# atxmega128a1.net
KiCad netlist of a schematic drawn in Altium Designer
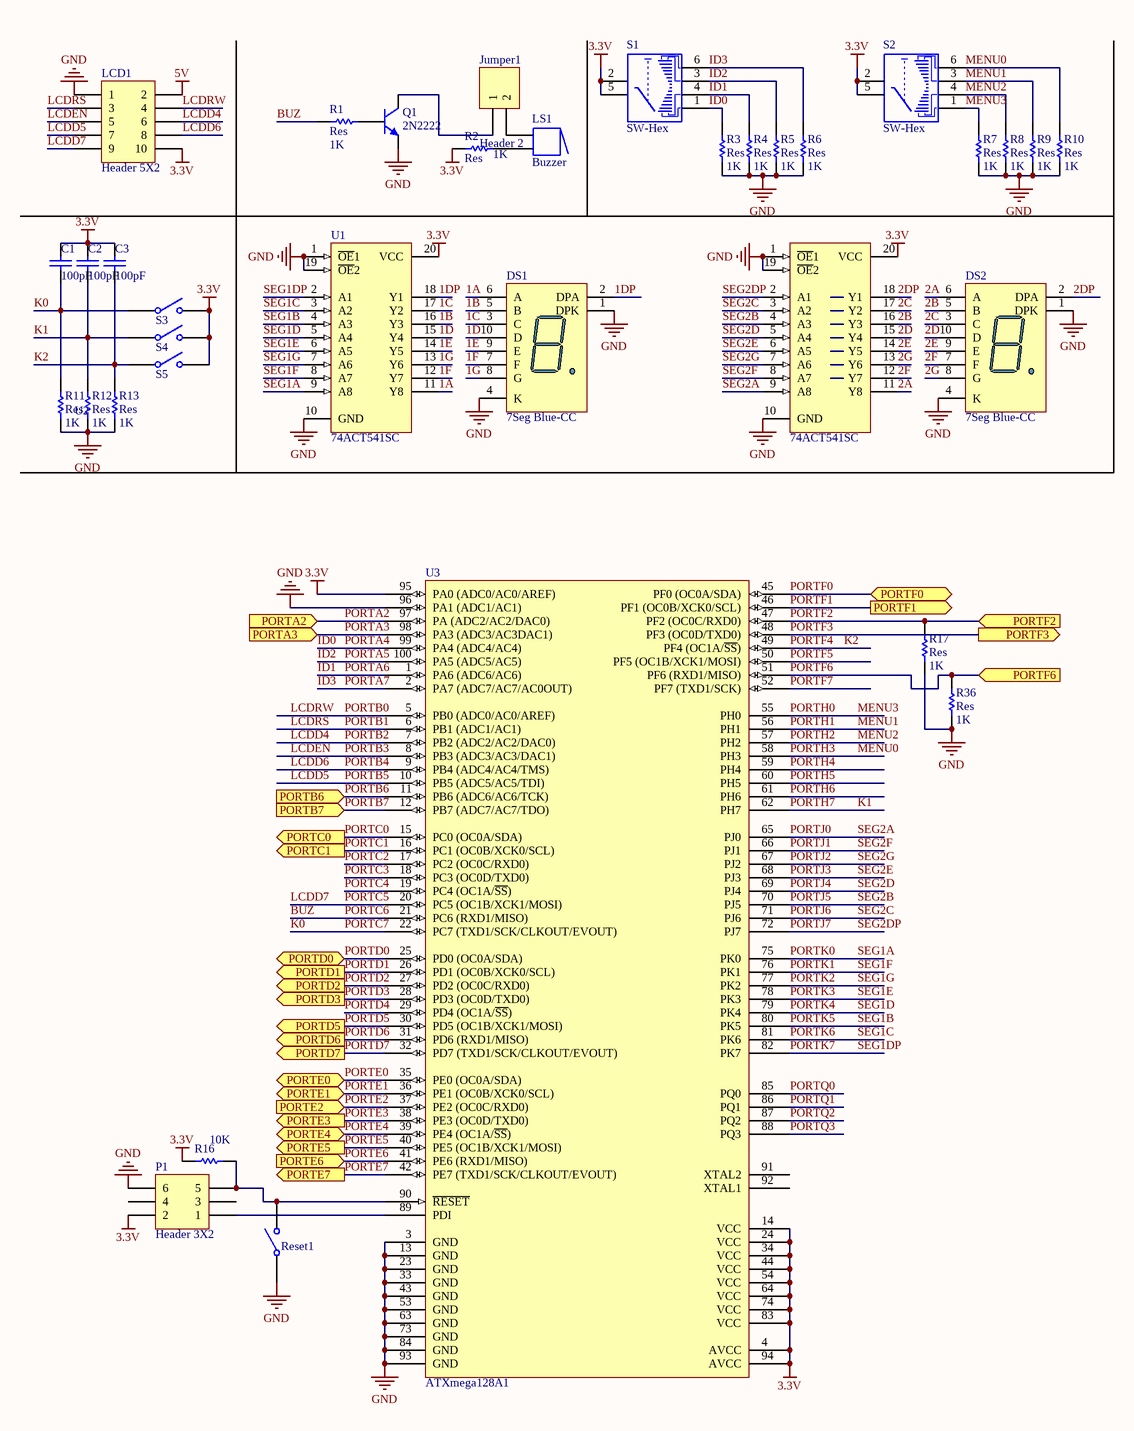
[diagram p0: atxmega128a1.SchDoc]

(export (version "E")
  (design (tool "Eeschema 10.0.6"))
  (components
    (comp (ref "C1")
      (value "100pF")
      (footprint "2012[0805]")
      (description "Capacitor")
      (fields (field (name "Comment") "Cap_UP") (field (name "PUBLISHER") "Altium Limited"))
      (libsource (lib "KN2CLib") (part "Cap_UP"))
    )
    (comp (ref "C2")
      (value "100pF")
      (footprint "2012[0805]")
      (description "Capacitor")
      (fields (field (name "Comment") "Cap_UP") (field (name "PUBLISHER") "Altium Limited"))
      (libsource (lib "KN2CLib") (part "Cap_UP"))
    )
    (comp (ref "C3")
      (value "100pF")
      (footprint "2012[0805]")
      (description "Capacitor")
      (fields (field (name "Comment") "Cap_UP") (field (name "PUBLISHER") "Altium Limited"))
      (libsource (lib "KN2CLib") (part "Cap_UP"))
    )
    (comp (ref "DS1")
      (value "7Seg Blue-CC")
      (footprint "7Segment Small")
      (description "14.2 mm General Purpose Blue 7-Segment Display: CC, RH DP, Gray Surface")
      (fields (field (name "PUBLISHER") "Altium Limited"))
      (libsource (lib "KN2CLib") (part "7Seg Blue-CC_1"))
    )
    (comp (ref "DS2")
      (value "7Seg Blue-CC")
      (footprint "7Segment Small")
      (description "14.2 mm General Purpose Blue 7-Segment Display: CC, RH DP, Gray Surface")
      (fields (field (name "PUBLISHER") "Altium Limited"))
      (libsource (lib "KN2CLib") (part "7Seg Blue-CC_1"))
    )
    (comp (ref "Jumper1")
      (value "Header 2")
      (footprint "HDR1X2")
      (description "Header, 2-Pin")
      (fields (field (name "PUBLISHER") "Altium Limited"))
      (libsource (lib "Miscellaneous Connectors") (part "Header 2"))
    )
    (comp (ref "LCD1")
      (value "Header 5X2")
      (footprint "HDRBOX2X5")
      (description "Header, 5-Pin, Dual row")
      (fields (field (name "PUBLISHER") "Altium Limited"))
      (libsource (lib "Miscellaneous Connectors") (part "Header 5X2"))
    )
    (comp (ref "LS1")
      (value "Buzzer")
      (footprint "BUZZER")
      (description "Magnetic Transducer Buzzer")
      (fields (field (name "PUBLISHER") "Altium Limited"))
      (libsource (lib "KN2CLib") (part "Buzzer"))
    )
    (comp (ref "P1")
      (value "Header 3X2")
      (footprint "HDRBOX2X3")
      (description "Header, 3-Pin, Dual row")
      (fields (field (name "PUBLISHER") "Altium Limited"))
      (libsource (lib "KN2CLib") (part "Header 3X2"))
    )
    (comp (ref "Q1")
      (value "2N2222")
      (footprint "SOT-23")
      (description "NPN Bipolar Transistor")
      (fields (field (name "PUBLISHER") "Altium Limited"))
      (libsource (lib "KN2CLib") (part "2N2222"))
    )
    (comp (ref "R1")
      (value "Res")
      (footprint "2012[0805]")
      (description "Semiconductor Resistor")
      (fields (field (name "ALTIUM_VALUE") "1K") (field (name "PUBLISHER") "Altium Limited"))
      (libsource (lib "KN2CLib") (part "Res"))
    )
    (comp (ref "R2")
      (value "Res")
      (footprint "2012[0805]")
      (description "Semiconductor Resistor")
      (fields (field (name "ALTIUM_VALUE") "1K") (field (name "PUBLISHER") "Altium Limited"))
      (libsource (lib "KN2CLib") (part "Res"))
    )
    (comp (ref "R3")
      (value "Res")
      (footprint "2012[0805]")
      (description "Semiconductor Resistor")
      (fields (field (name "ALTIUM_VALUE") "1K") (field (name "PUBLISHER") "Altium Limited"))
      (libsource (lib "KN2CLib") (part "Res"))
    )
    (comp (ref "R4")
      (value "Res")
      (footprint "2012[0805]")
      (description "Semiconductor Resistor")
      (fields (field (name "ALTIUM_VALUE") "1K") (field (name "PUBLISHER") "Altium Limited"))
      (libsource (lib "KN2CLib") (part "Res"))
    )
    (comp (ref "R5")
      (value "Res")
      (footprint "2012[0805]")
      (description "Semiconductor Resistor")
      (fields (field (name "ALTIUM_VALUE") "1K") (field (name "PUBLISHER") "Altium Limited"))
      (libsource (lib "KN2CLib") (part "Res"))
    )
    (comp (ref "R6")
      (value "Res")
      (footprint "2012[0805]")
      (description "Semiconductor Resistor")
      (fields (field (name "ALTIUM_VALUE") "1K") (field (name "PUBLISHER") "Altium Limited"))
      (libsource (lib "KN2CLib") (part "Res"))
    )
    (comp (ref "R7")
      (value "Res")
      (footprint "2012[0805]")
      (description "Semiconductor Resistor")
      (fields (field (name "ALTIUM_VALUE") "1K") (field (name "PUBLISHER") "Altium Limited"))
      (libsource (lib "KN2CLib") (part "Res"))
    )
    (comp (ref "R8")
      (value "Res")
      (footprint "2012[0805]")
      (description "Semiconductor Resistor")
      (fields (field (name "ALTIUM_VALUE") "1K") (field (name "PUBLISHER") "Altium Limited"))
      (libsource (lib "KN2CLib") (part "Res"))
    )
    (comp (ref "R9")
      (value "Res")
      (footprint "2012[0805]")
      (description "Semiconductor Resistor")
      (fields (field (name "ALTIUM_VALUE") "1K") (field (name "PUBLISHER") "Altium Limited"))
      (libsource (lib "KN2CLib") (part "Res"))
    )
    (comp (ref "R10")
      (value "Res")
      (footprint "2012[0805]")
      (description "Semiconductor Resistor")
      (fields (field (name "ALTIUM_VALUE") "1K") (field (name "PUBLISHER") "Altium Limited"))
      (libsource (lib "KN2CLib") (part "Res"))
    )
    (comp (ref "R11")
      (value "Res")
      (footprint "2012[0805]")
      (description "Semiconductor Resistor")
      (fields (field (name "ALTIUM_VALUE") "1K") (field (name "PUBLISHER") "Altium Limited"))
      (libsource (lib "KN2CLib") (part "Res"))
    )
    (comp (ref "R12")
      (value "Res")
      (footprint "2012[0805]")
      (description "Semiconductor Resistor")
      (fields (field (name "ALTIUM_VALUE") "1K") (field (name "PUBLISHER") "Altium Limited"))
      (libsource (lib "KN2CLib") (part "Res"))
    )
    (comp (ref "R13")
      (value "Res")
      (footprint "2012[0805]")
      (description "Semiconductor Resistor")
      (fields (field (name "ALTIUM_VALUE") "1K") (field (name "PUBLISHER") "Altium Limited"))
      (libsource (lib "KN2CLib") (part "Res"))
    )
    (comp (ref "R16")
      (value "10K")
      (footprint "2012[0805]")
      (description "Semiconductor Resistor")
      (fields (field (name "PUBLISHER") "Altium Limited"))
      (libsource (lib "KN2CLib") (part "Res"))
    )
    (comp (ref "R17")
      (value "Res")
      (footprint "2012[0805]")
      (description "Semiconductor Resistor")
      (fields (field (name "ALTIUM_VALUE") "1K") (field (name "PUBLISHER") "Altium Limited"))
      (libsource (lib "KN2CLib") (part "Res"))
    )
    (comp (ref "R36")
      (value "Res")
      (footprint "2012[0805]")
      (description "Semiconductor Resistor")
      (fields (field (name "ALTIUM_VALUE") "1K") (field (name "PUBLISHER") "Altium Limited"))
      (libsource (lib "KN2CLib") (part "Res"))
    )
    (comp (ref "Reset1")
      (value "SW-SPST")
      (footprint "PUSH-BUT")
      (description "Single-Pole, Single-Throw Switch")
      (fields (field (name "PUBLISHER") "Altium Limited"))
      (libsource (lib "KN2CLib") (part "SW-SPST"))
    )
    (comp (ref "S1")
      (value "SW-Hex")
      (footprint "SW-HEX")
      (fields (field (name "PUBLISHER") "Altium Limited"))
      (libsource (lib "KN2CLib") (part "SW-Hex"))
    )
    (comp (ref "S2")
      (value "SW-Hex")
      (footprint "SW-HEX")
      (fields (field (name "PUBLISHER") "Altium Limited"))
      (libsource (lib "KN2CLib") (part "SW-Hex"))
    )
    (comp (ref "S3")
      (value "SW-SPST")
      (footprint "PUSH-BUT")
      (description "Single-Pole, Single-Throw Switch")
      (fields (field (name "PUBLISHER") "Altium Limited"))
      (libsource (lib "KN2CLib") (part "SW-SPST"))
    )
    (comp (ref "S4")
      (value "SW-SPST")
      (footprint "PUSH-BUT")
      (description "Single-Pole, Single-Throw Switch")
      (fields (field (name "PUBLISHER") "Altium Limited"))
      (libsource (lib "KN2CLib") (part "SW-SPST"))
    )
    (comp (ref "S5")
      (value "SW-SPST")
      (footprint "PUSH-BUT")
      (description "Single-Pole, Single-Throw Switch")
      (fields (field (name "PUBLISHER") "Altium Limited"))
      (libsource (lib "KN2CLib") (part "SW-SPST"))
    )
    (comp (ref "U1")
      (value "74ACT541SC")
      (footprint "M20B_M")
      (description "Octal Buffer/Line Driver with 3-State Output")
      (fields (field (name "PUBLISHER") "Altium Limited"))
      (libsource (lib "FSC Logic Buffer Line Driver") (part "74ACT541SC"))
    )
    (comp (ref "U2")
      (value "74ACT541SC")
      (footprint "M20B_M")
      (description "Octal Buffer/Line Driver with 3-State Output")
      (fields (field (name "PUBLISHER") "Altium Limited"))
      (libsource (lib "FSC Logic Buffer Line Driver") (part "74ACT541SC"))
    )
    (comp (ref "U3")
      (value "ATXmega128A1")
      (footprint "100A_N")
      (libsource (lib "KN2CLib") (part "ATXmega128A1"))
    )
  )
  (nets
    (net (code "1") (name "/1A") (class "Default")
      (node (ref "DS1") (pin "6") (pinfunction "A_6") (pintype "passive"))
      (node (ref "U1") (pin "11") (pinfunction "Y8_11") (pintype "tri_state"))
    )
    (net (code "2") (name "/1B") (class "Default")
      (node (ref "DS1") (pin "5") (pinfunction "B_5") (pintype "passive"))
      (node (ref "U1") (pin "16") (pinfunction "Y3_16") (pintype "tri_state"))
    )
    (net (code "3") (name "/1C") (class "Default")
      (node (ref "DS1") (pin "3") (pinfunction "C_3") (pintype "passive"))
      (node (ref "U1") (pin "17") (pinfunction "Y2_17") (pintype "tri_state"))
    )
    (net (code "4") (name "/1D") (class "Default")
      (node (ref "DS1") (pin "10") (pinfunction "D_10") (pintype "passive"))
      (node (ref "U1") (pin "15") (pinfunction "Y4_15") (pintype "tri_state"))
    )
    (net (code "5") (name "/1DP") (class "Default")
      (node (ref "DS1") (pin "2") (pinfunction "DPA_2") (pintype "passive"))
      (node (ref "U1") (pin "18") (pinfunction "Y1_18") (pintype "tri_state"))
    )
    (net (code "6") (name "/1E") (class "Default")
      (node (ref "DS1") (pin "9") (pinfunction "E_9") (pintype "passive"))
      (node (ref "U1") (pin "14") (pinfunction "Y5_14") (pintype "tri_state"))
    )
    (net (code "7") (name "/1F") (class "Default")
      (node (ref "DS1") (pin "7") (pinfunction "F_7") (pintype "passive"))
      (node (ref "U1") (pin "12") (pinfunction "Y7_12") (pintype "tri_state"))
    )
    (net (code "8") (name "/1G") (class "Default")
      (node (ref "DS1") (pin "8") (pinfunction "G_8") (pintype "passive"))
      (node (ref "U1") (pin "13") (pinfunction "Y6_13") (pintype "tri_state"))
    )
    (net (code "9") (name "/2A") (class "Default")
      (node (ref "DS2") (pin "6") (pinfunction "A_6") (pintype "passive"))
      (node (ref "U2") (pin "11") (pinfunction "Y8_11") (pintype "tri_state"))
    )
    (net (code "10") (name "/2B") (class "Default")
      (node (ref "DS2") (pin "5") (pinfunction "B_5") (pintype "passive"))
      (node (ref "U2") (pin "16") (pinfunction "Y3_16") (pintype "tri_state"))
    )
    (net (code "11") (name "/2C") (class "Default")
      (node (ref "DS2") (pin "3") (pinfunction "C_3") (pintype "passive"))
      (node (ref "U2") (pin "17") (pinfunction "Y2_17") (pintype "tri_state"))
    )
    (net (code "12") (name "/2D") (class "Default")
      (node (ref "DS2") (pin "10") (pinfunction "D_10") (pintype "passive"))
      (node (ref "U2") (pin "15") (pinfunction "Y4_15") (pintype "tri_state"))
    )
    (net (code "13") (name "/2DP") (class "Default")
      (node (ref "DS2") (pin "2") (pinfunction "DPA_2") (pintype "passive"))
      (node (ref "U2") (pin "18") (pinfunction "Y1_18") (pintype "tri_state"))
    )
    (net (code "14") (name "/2E") (class "Default")
      (node (ref "DS2") (pin "9") (pinfunction "E_9") (pintype "passive"))
      (node (ref "U2") (pin "14") (pinfunction "Y5_14") (pintype "tri_state"))
    )
    (net (code "15") (name "/2F") (class "Default")
      (node (ref "DS2") (pin "7") (pinfunction "F_7") (pintype "passive"))
      (node (ref "U2") (pin "12") (pinfunction "Y7_12") (pintype "tri_state"))
    )
    (net (code "16") (name "/2G") (class "Default")
      (node (ref "DS2") (pin "8") (pinfunction "G_8") (pintype "passive"))
      (node (ref "U2") (pin "13") (pinfunction "Y6_13") (pintype "tri_state"))
    )
    (net (code "17") (name "/BUZ") (class "Default")
      (node (ref "R1") (pin "1") (pinfunction "1_1") (pintype "passive"))
      (node (ref "U3") (pin "21") (pinfunction "PC6_(RXD1/MISO)_21") (pintype "bidirectional"))
    )
    (net (code "18") (name "/ID0") (class "Default")
      (node (ref "R3") (pin "2") (pinfunction "2_2") (pintype "passive"))
      (node (ref "S1") (pin "1") (pinfunction "1_1") (pintype "passive"))
      (node (ref "U3") (pin "99") (pinfunction "PA4_(ADC4/AC4)_99") (pintype "bidirectional"))
    )
    (net (code "19") (name "/ID1") (class "Default")
      (node (ref "R4") (pin "2") (pinfunction "2_2") (pintype "passive"))
      (node (ref "S1") (pin "4") (pinfunction "4_4") (pintype "passive"))
      (node (ref "U3") (pin "1") (pinfunction "PA6_(ADC6/AC6)_1") (pintype "bidirectional"))
    )
    (net (code "20") (name "/ID2") (class "Default")
      (node (ref "R5") (pin "2") (pinfunction "2_2") (pintype "passive"))
      (node (ref "S1") (pin "3") (pinfunction "3_3") (pintype "passive"))
      (node (ref "U3") (pin "100") (pinfunction "PA5_(ADC5/AC5)_100") (pintype "bidirectional"))
    )
    (net (code "21") (name "/ID3") (class "Default")
      (node (ref "R6") (pin "2") (pinfunction "2_2") (pintype "passive"))
      (node (ref "S1") (pin "6") (pinfunction "6_6") (pintype "passive"))
      (node (ref "U3") (pin "2") (pinfunction "PA7_(ADC7/AC7/AC0OUT)_2") (pintype "bidirectional"))
    )
    (net (code "22") (name "/K0") (class "Default")
      (node (ref "C1") (pin "1") (pinfunction "1_1") (pintype "passive"))
      (node (ref "R11") (pin "1") (pinfunction "1_1") (pintype "passive"))
      (node (ref "S3") (pin "1") (pinfunction "COMMON_1") (pintype "passive"))
      (node (ref "U3") (pin "22") (pinfunction "PC7_(TXD1/SCK/CLKOUT/EVOUT)_22") (pintype "bidirectional"))
    )
    (net (code "23") (name "/K1") (class "Default")
      (node (ref "C2") (pin "1") (pinfunction "1_1") (pintype "passive"))
      (node (ref "R12") (pin "1") (pinfunction "1_1") (pintype "passive"))
      (node (ref "S4") (pin "1") (pinfunction "COMMON_1") (pintype "passive"))
      (node (ref "U3") (pin "62") (pinfunction "PH7_62") (pintype "passive"))
    )
    (net (code "24") (name "/K2") (class "Default")
      (node (ref "C3") (pin "1") (pinfunction "1_1") (pintype "passive"))
      (node (ref "R13") (pin "1") (pinfunction "1_1") (pintype "passive"))
      (node (ref "S5") (pin "1") (pinfunction "COMMON_1") (pintype "passive"))
      (node (ref "U3") (pin "49") (pinfunction "PF4_(OC1A/~{SS})_49") (pintype "bidirectional"))
    )
    (net (code "25") (name "/LCDD4") (class "Default")
      (node (ref "LCD1") (pin "6") (pinfunction "6_6") (pintype "passive"))
      (node (ref "U3") (pin "7") (pinfunction "PB2_(ADC2/AC2/DAC0)_7") (pintype "bidirectional"))
    )
    (net (code "26") (name "/LCDD5") (class "Default")
      (node (ref "LCD1") (pin "7") (pinfunction "7_7") (pintype "passive"))
      (node (ref "U3") (pin "10") (pinfunction "PB5_(ADC5/AC5/TDI)_10") (pintype "bidirectional"))
    )
    (net (code "27") (name "/LCDD6") (class "Default")
      (node (ref "LCD1") (pin "8") (pinfunction "8_8") (pintype "passive"))
      (node (ref "U3") (pin "9") (pinfunction "PB4_(ADC4/AC4/TMS)_9") (pintype "bidirectional"))
    )
    (net (code "28") (name "/LCDD7") (class "Default")
      (node (ref "LCD1") (pin "9") (pinfunction "9_9") (pintype "passive"))
      (node (ref "U3") (pin "20") (pinfunction "PC5_(OC1B/XCK1/MOSI)_20") (pintype "bidirectional"))
    )
    (net (code "29") (name "/LCDEN") (class "Default")
      (node (ref "LCD1") (pin "5") (pinfunction "5_5") (pintype "passive"))
      (node (ref "U3") (pin "8") (pinfunction "PB3_(ADC3/AC3/DAC1)_8") (pintype "bidirectional"))
    )
    (net (code "30") (name "/LCDRS") (class "Default")
      (node (ref "LCD1") (pin "3") (pinfunction "3_3") (pintype "passive"))
      (node (ref "U3") (pin "6") (pinfunction "PB1_(ADC1/AC1)_6") (pintype "bidirectional"))
    )
    (net (code "31") (name "/LCDRW") (class "Default")
      (node (ref "LCD1") (pin "4") (pinfunction "4_4") (pintype "passive"))
      (node (ref "U3") (pin "5") (pinfunction "PB0_(ADC0/AC0/AREF)_5") (pintype "bidirectional"))
    )
    (net (code "32") (name "/MENU0") (class "Default")
      (node (ref "R10") (pin "2") (pinfunction "2_2") (pintype "passive"))
      (node (ref "S2") (pin "6") (pinfunction "6_6") (pintype "passive"))
      (node (ref "U3") (pin "58") (pinfunction "PH3_58") (pintype "passive"))
    )
    (net (code "33") (name "/MENU1") (class "Default")
      (node (ref "R9") (pin "2") (pinfunction "2_2") (pintype "passive"))
      (node (ref "S2") (pin "3") (pinfunction "3_3") (pintype "passive"))
      (node (ref "U3") (pin "56") (pinfunction "PH1_56") (pintype "passive"))
    )
    (net (code "34") (name "/MENU2") (class "Default")
      (node (ref "R8") (pin "2") (pinfunction "2_2") (pintype "passive"))
      (node (ref "S2") (pin "4") (pinfunction "4_4") (pintype "passive"))
      (node (ref "U3") (pin "57") (pinfunction "PH2_57") (pintype "passive"))
    )
    (net (code "35") (name "/MENU3") (class "Default")
      (node (ref "R7") (pin "2") (pinfunction "2_2") (pintype "passive"))
      (node (ref "S2") (pin "1") (pinfunction "1_1") (pintype "passive"))
      (node (ref "U3") (pin "55") (pinfunction "PH0_55") (pintype "passive"))
    )
    (net (code "36") (name "/PORTA2") (class "Default")
      (node (ref "U3") (pin "97") (pinfunction "PA_(ADC2/AC2/DAC0)_97") (pintype "bidirectional"))
    )
    (net (code "37") (name "/PORTA3") (class "Default")
      (node (ref "U3") (pin "98") (pinfunction "PA3_(ADC3/AC3DAC1)_98") (pintype "bidirectional"))
    )
    (net (code "38") (name "/PORTB6") (class "Default")
      (node (ref "U3") (pin "11") (pinfunction "PB6_(ADC6/AC6/TCK)_11") (pintype "bidirectional"))
    )
    (net (code "39") (name "/PORTB7") (class "Default")
      (node (ref "U3") (pin "12") (pinfunction "PB7_(ADC7/AC7/TDO)_12") (pintype "bidirectional"))
    )
    (net (code "40") (name "/PORTC0") (class "Default")
      (node (ref "U3") (pin "15") (pinfunction "PC0_(OC0A/SDA)_15") (pintype "bidirectional"))
    )
    (net (code "41") (name "/PORTC1") (class "Default")
      (node (ref "U3") (pin "16") (pinfunction "PC1_(OC0B/XCK0/SCL)_16") (pintype "bidirectional"))
    )
    (net (code "42") (name "/PORTC2") (class "Default")
      (node (ref "U3") (pin "17") (pinfunction "PC2_(OC0C/RXD0)_17") (pintype "bidirectional"))
    )
    (net (code "43") (name "/PORTC3") (class "Default")
      (node (ref "U3") (pin "18") (pinfunction "PC3_(OC0D/TXD0)_18") (pintype "bidirectional"))
    )
    (net (code "44") (name "/PORTC4") (class "Default")
      (node (ref "U3") (pin "19") (pinfunction "PC4_(OC1A/~{SS})_19") (pintype "bidirectional"))
    )
    (net (code "45") (name "/PORTD0") (class "Default")
      (node (ref "U3") (pin "25") (pinfunction "PD0_(OC0A/SDA)_25") (pintype "bidirectional"))
    )
    (net (code "46") (name "/PORTD1") (class "Default")
      (node (ref "U3") (pin "26") (pinfunction "PD1_(OC0B/XCK0/SCL)_26") (pintype "bidirectional"))
    )
    (net (code "47") (name "/PORTD2") (class "Default")
      (node (ref "U3") (pin "27") (pinfunction "PD2_(OC0C/RXD0)_27") (pintype "bidirectional"))
    )
    (net (code "48") (name "/PORTD3") (class "Default")
      (node (ref "U3") (pin "28") (pinfunction "PD3_(OC0D/TXD0)_28") (pintype "bidirectional"))
    )
    (net (code "49") (name "/PORTD4") (class "Default")
      (node (ref "U3") (pin "29") (pinfunction "PD4_(OC1A/~{SS})_29") (pintype "bidirectional"))
    )
    (net (code "50") (name "/PORTD5") (class "Default")
      (node (ref "U3") (pin "30") (pinfunction "PD5_(OC1B/XCK1/MOSI)_30") (pintype "bidirectional"))
    )
    (net (code "51") (name "/PORTD6") (class "Default")
      (node (ref "U3") (pin "31") (pinfunction "PD6_(RXD1/MISO)_31") (pintype "bidirectional"))
    )
    (net (code "52") (name "/PORTD7") (class "Default")
      (node (ref "U3") (pin "32") (pinfunction "PD7_(TXD1/SCK/CLKOUT/EVOUT)_32") (pintype "bidirectional"))
    )
    (net (code "53") (name "/PORTE0") (class "Default")
      (node (ref "U3") (pin "35") (pinfunction "PE0_(OC0A/SDA)_35") (pintype "bidirectional"))
    )
    (net (code "54") (name "/PORTE1") (class "Default")
      (node (ref "U3") (pin "36") (pinfunction "PE1_(OC0B/XCK0/SCL)_36") (pintype "bidirectional"))
    )
    (net (code "55") (name "/PORTE2") (class "Default")
      (node (ref "U3") (pin "37") (pinfunction "PE2_(OC0C/RXD0)_37") (pintype "bidirectional"))
    )
    (net (code "56") (name "/PORTE3") (class "Default")
      (node (ref "U3") (pin "38") (pinfunction "PE3_(OC0D/TXD0)_38") (pintype "bidirectional"))
    )
    (net (code "57") (name "/PORTE4") (class "Default")
      (node (ref "U3") (pin "39") (pinfunction "PE4_(OC1A/~{SS})_39") (pintype "bidirectional"))
    )
    (net (code "58") (name "/PORTE5") (class "Default")
      (node (ref "U3") (pin "40") (pinfunction "PE5_(OC1B/XCK1/MOSI)_40") (pintype "bidirectional"))
    )
    (net (code "59") (name "/PORTE6") (class "Default")
      (node (ref "U3") (pin "41") (pinfunction "PE6_(RXD1/MISO)_41") (pintype "bidirectional"))
    )
    (net (code "60") (name "/PORTE7") (class "Default")
      (node (ref "U3") (pin "42") (pinfunction "PE7_(TXD1/SCK/CLKOUT/EVOUT)_42") (pintype "bidirectional"))
    )
    (net (code "61") (name "/PORTF0") (class "Default")
      (node (ref "U3") (pin "45") (pinfunction "PF0_(OC0A/SDA)_45") (pintype "bidirectional"))
    )
    (net (code "62") (name "/PORTF1") (class "Default")
      (node (ref "U3") (pin "46") (pinfunction "PF1_(OC0B/XCK0/SCL)_46") (pintype "bidirectional"))
    )
    (net (code "63") (name "/PORTF2") (class "Default")
      (node (ref "R17") (pin "2") (pinfunction "2_2") (pintype "passive"))
      (node (ref "U3") (pin "47") (pinfunction "PF2_(OC0C/RXD0)_47") (pintype "bidirectional"))
    )
    (net (code "64") (name "/PORTF3") (class "Default")
      (node (ref "U3") (pin "48") (pinfunction "PF3_(OC0D/TXD0)_48") (pintype "bidirectional"))
    )
    (net (code "65") (name "/PORTF5") (class "Default")
      (node (ref "U3") (pin "50") (pinfunction "PF5_(OC1B/XCK1/MOSI)_50") (pintype "bidirectional"))
    )
    (net (code "66") (name "/PORTF6") (class "Default")
      (node (ref "R36") (pin "2") (pinfunction "2_2") (pintype "passive"))
      (node (ref "U3") (pin "51") (pinfunction "PF6_(RXD1/MISO)_51") (pintype "bidirectional"))
    )
    (net (code "67") (name "/PORTF7") (class "Default")
      (node (ref "U3") (pin "52") (pinfunction "PF7_(TXD1/SCK)_52") (pintype "bidirectional"))
    )
    (net (code "68") (name "/PORTH4") (class "Default")
      (node (ref "U3") (pin "59") (pinfunction "PH4_59") (pintype "passive"))
    )
    (net (code "69") (name "/PORTH5") (class "Default")
      (node (ref "U3") (pin "60") (pinfunction "PH5_60") (pintype "passive"))
    )
    (net (code "70") (name "/PORTH6") (class "Default")
      (node (ref "U3") (pin "61") (pinfunction "PH6_61") (pintype "passive"))
    )
    (net (code "71") (name "/PORTJ0") (class "Default")
      (node (ref "U2") (pin "9") (pinfunction "A8_9") (pintype "input"))
      (node (ref "U3") (pin "65") (pinfunction "PJ0_65") (pintype "passive"))
    )
    (net (code "72") (name "/PORTJ1") (class "Default")
      (node (ref "U2") (pin "8") (pinfunction "A7_8") (pintype "input"))
      (node (ref "U3") (pin "66") (pinfunction "PJ1_66") (pintype "passive"))
    )
    (net (code "73") (name "/PORTJ2") (class "Default")
      (node (ref "U2") (pin "7") (pinfunction "A6_7") (pintype "input"))
      (node (ref "U3") (pin "67") (pinfunction "PJ2_67") (pintype "passive"))
    )
    (net (code "74") (name "/PORTJ3") (class "Default")
      (node (ref "U2") (pin "6") (pinfunction "A5_6") (pintype "input"))
      (node (ref "U3") (pin "68") (pinfunction "PJ3_68") (pintype "passive"))
    )
    (net (code "75") (name "/PORTJ4") (class "Default")
      (node (ref "U2") (pin "5") (pinfunction "A4_5") (pintype "input"))
      (node (ref "U3") (pin "69") (pinfunction "PJ4_69") (pintype "passive"))
    )
    (net (code "76") (name "/PORTJ5") (class "Default")
      (node (ref "U2") (pin "4") (pinfunction "A3_4") (pintype "input"))
      (node (ref "U3") (pin "70") (pinfunction "PJ5_70") (pintype "passive"))
    )
    (net (code "77") (name "/PORTJ6") (class "Default")
      (node (ref "U2") (pin "3") (pinfunction "A2_3") (pintype "input"))
      (node (ref "U3") (pin "71") (pinfunction "PJ6_71") (pintype "passive"))
    )
    (net (code "78") (name "/PORTJ7") (class "Default")
      (node (ref "U2") (pin "2") (pinfunction "A1_2") (pintype "input"))
      (node (ref "U3") (pin "72") (pinfunction "PJ7_72") (pintype "passive"))
    )
    (net (code "79") (name "/PORTK0") (class "Default")
      (node (ref "U1") (pin "9") (pinfunction "A8_9") (pintype "input"))
      (node (ref "U3") (pin "75") (pinfunction "PK0_75") (pintype "passive"))
    )
    (net (code "80") (name "/PORTK1") (class "Default")
      (node (ref "U1") (pin "8") (pinfunction "A7_8") (pintype "input"))
      (node (ref "U3") (pin "76") (pinfunction "PK1_76") (pintype "passive"))
    )
    (net (code "81") (name "/PORTK2") (class "Default")
      (node (ref "U1") (pin "7") (pinfunction "A6_7") (pintype "input"))
      (node (ref "U3") (pin "77") (pinfunction "PK2_77") (pintype "passive"))
    )
    (net (code "82") (name "/PORTK3") (class "Default")
      (node (ref "U1") (pin "6") (pinfunction "A5_6") (pintype "input"))
      (node (ref "U3") (pin "78") (pinfunction "PK3_78") (pintype "passive"))
    )
    (net (code "83") (name "/PORTK4") (class "Default")
      (node (ref "U1") (pin "5") (pinfunction "A4_5") (pintype "input"))
      (node (ref "U3") (pin "79") (pinfunction "PK4_79") (pintype "passive"))
    )
    (net (code "84") (name "/PORTK5") (class "Default")
      (node (ref "U1") (pin "4") (pinfunction "A3_4") (pintype "input"))
      (node (ref "U3") (pin "80") (pinfunction "PK5_80") (pintype "passive"))
    )
    (net (code "85") (name "/PORTK6") (class "Default")
      (node (ref "U1") (pin "3") (pinfunction "A2_3") (pintype "input"))
      (node (ref "U3") (pin "81") (pinfunction "PK6_81") (pintype "passive"))
    )
    (net (code "86") (name "/PORTK7") (class "Default")
      (node (ref "U1") (pin "2") (pinfunction "A1_2") (pintype "input"))
      (node (ref "U3") (pin "82") (pinfunction "PK7_82") (pintype "passive"))
    )
    (net (code "87") (name "/PORTQ0") (class "Default")
      (node (ref "U3") (pin "85") (pinfunction "PQ0_85") (pintype "passive"))
    )
    (net (code "88") (name "/PORTQ1") (class "Default")
      (node (ref "U3") (pin "86") (pinfunction "PQ1_86") (pintype "passive"))
    )
    (net (code "89") (name "/PORTQ2") (class "Default")
      (node (ref "U3") (pin "87") (pinfunction "PQ2_87") (pintype "passive"))
    )
    (net (code "90") (name "/PORTQ3") (class "Default")
      (node (ref "U3") (pin "88") (pinfunction "PQ3_88") (pintype "passive"))
    )
    (net (code "91") (name "3.3V") (class "Default")
      (node (ref "C1") (pin "2") (pinfunction "2_2") (pintype "passive"))
      (node (ref "C2") (pin "2") (pinfunction "2_2") (pintype "passive"))
      (node (ref "C3") (pin "2") (pinfunction "2_2") (pintype "passive"))
      (node (ref "LCD1") (pin "10") (pinfunction "10_10") (pintype "passive"))
      (node (ref "P1") (pin "2") (pinfunction "2_2") (pintype "passive"))
      (node (ref "R16") (pin "1") (pinfunction "1_1") (pintype "passive"))
      (node (ref "R2") (pin "1") (pinfunction "1_1") (pintype "passive"))
      (node (ref "S1") (pin "2") (pinfunction "2_2") (pintype "passive"))
      (node (ref "S1") (pin "5") (pinfunction "5_5") (pintype "passive"))
      (node (ref "S2") (pin "2") (pinfunction "2_2") (pintype "passive"))
      (node (ref "S2") (pin "5") (pinfunction "5_5") (pintype "passive"))
      (node (ref "S3") (pin "2") (pinfunction "NO_2") (pintype "passive"))
      (node (ref "S4") (pin "2") (pinfunction "NO_2") (pintype "passive"))
      (node (ref "S5") (pin "2") (pinfunction "NO_2") (pintype "passive"))
      (node (ref "U1") (pin "20") (pinfunction "VCC_20") (pintype "power_in"))
      (node (ref "U2") (pin "20") (pinfunction "VCC_20") (pintype "power_in"))
      (node (ref "U3") (pin "14") (pinfunction "VCC_14") (pintype "power_in"))
      (node (ref "U3") (pin "24") (pinfunction "VCC_24") (pintype "power_in"))
      (node (ref "U3") (pin "34") (pinfunction "VCC_34") (pintype "power_in"))
      (node (ref "U3") (pin "4") (pinfunction "AVCC_4") (pintype "power_in"))
      (node (ref "U3") (pin "44") (pinfunction "VCC_44") (pintype "power_in"))
      (node (ref "U3") (pin "54") (pinfunction "VCC_54") (pintype "passive"))
      (node (ref "U3") (pin "64") (pinfunction "VCC_64") (pintype "passive"))
      (node (ref "U3") (pin "74") (pinfunction "VCC_74") (pintype "passive"))
      (node (ref "U3") (pin "83") (pinfunction "VCC_83") (pintype "passive"))
      (node (ref "U3") (pin "94") (pinfunction "AVCC_94") (pintype "power_in"))
      (node (ref "U3") (pin "95") (pinfunction "PA0_(ADC0/AC0/AREF)_95") (pintype "bidirectional"))
    )
    (net (code "92") (name "5V") (class "Default")
      (node (ref "LCD1") (pin "2") (pinfunction "2_2") (pintype "passive"))
    )
    (net (code "93") (name "GND") (class "Default")
      (node (ref "DS1") (pin "1") (pinfunction "DPK_1") (pintype "passive"))
      (node (ref "DS1") (pin "4") (pinfunction "K_4") (pintype "passive"))
      (node (ref "DS2") (pin "1") (pinfunction "DPK_1") (pintype "passive"))
      (node (ref "DS2") (pin "4") (pinfunction "K_4") (pintype "passive"))
      (node (ref "LCD1") (pin "1") (pinfunction "1_1") (pintype "passive"))
      (node (ref "P1") (pin "6") (pinfunction "6_6") (pintype "passive"))
      (node (ref "Q1") (pin "3") (pinfunction "E_3") (pintype "passive"))
      (node (ref "R10") (pin "1") (pinfunction "1_1") (pintype "passive"))
      (node (ref "R11") (pin "2") (pinfunction "2_2") (pintype "passive"))
      (node (ref "R12") (pin "2") (pinfunction "2_2") (pintype "passive"))
      (node (ref "R13") (pin "2") (pinfunction "2_2") (pintype "passive"))
      (node (ref "R17") (pin "1") (pinfunction "1_1") (pintype "passive"))
      (node (ref "R3") (pin "1") (pinfunction "1_1") (pintype "passive"))
      (node (ref "R36") (pin "1") (pinfunction "1_1") (pintype "passive"))
      (node (ref "R4") (pin "1") (pinfunction "1_1") (pintype "passive"))
      (node (ref "R5") (pin "1") (pinfunction "1_1") (pintype "passive"))
      (node (ref "R6") (pin "1") (pinfunction "1_1") (pintype "passive"))
      (node (ref "R7") (pin "1") (pinfunction "1_1") (pintype "passive"))
      (node (ref "R8") (pin "1") (pinfunction "1_1") (pintype "passive"))
      (node (ref "R9") (pin "1") (pinfunction "1_1") (pintype "passive"))
      (node (ref "Reset1") (pin "1") (pinfunction "COMMON_1") (pintype "passive"))
      (node (ref "U1") (pin "1") (pinfunction "~{OE}1_1") (pintype "input"))
      (node (ref "U1") (pin "10") (pinfunction "GND_10") (pintype "power_in"))
      (node (ref "U1") (pin "19") (pinfunction "~{OE}2_19") (pintype "input"))
      (node (ref "U2") (pin "1") (pinfunction "~{OE}1_1") (pintype "input"))
      (node (ref "U2") (pin "10") (pinfunction "GND_10") (pintype "power_in"))
      (node (ref "U2") (pin "19") (pinfunction "~{OE}2_19") (pintype "input"))
      (node (ref "U3") (pin "13") (pinfunction "GND_13") (pintype "power_in"))
      (node (ref "U3") (pin "23") (pinfunction "GND_23") (pintype "power_in"))
      (node (ref "U3") (pin "3") (pinfunction "GND_3") (pintype "power_in"))
      (node (ref "U3") (pin "33") (pinfunction "GND_33") (pintype "power_in"))
      (node (ref "U3") (pin "43") (pinfunction "GND_43") (pintype "power_in"))
      (node (ref "U3") (pin "53") (pinfunction "GND_53") (pintype "power_in"))
      (node (ref "U3") (pin "63") (pinfunction "GND_63") (pintype "passive"))
      (node (ref "U3") (pin "73") (pinfunction "GND_73") (pintype "passive"))
      (node (ref "U3") (pin "84") (pinfunction "GND_84") (pintype "passive"))
      (node (ref "U3") (pin "93") (pinfunction "GND_93") (pintype "passive"))
      (node (ref "U3") (pin "96") (pinfunction "PA1_(ADC1/AC1)_96") (pintype "bidirectional"))
    )
    (net (code "94") (name "Net-(Jumper1-Pad2)") (class "Default")
      (node (ref "Jumper1") (pin "2") (pinfunction "2_2") (pintype "passive"))
      (node (ref "LS1") (pin "1") (pinfunction "1_1") (pintype "passive"))
    )
    (net (code "95") (name "Net-(LS1-Pad2)") (class "Default")
      (node (ref "LS1") (pin "2") (pinfunction "2_2") (pintype "passive"))
      (node (ref "R2") (pin "2") (pinfunction "2_2") (pintype "passive"))
    )
    (net (code "96") (name "Net-(Q1-B)") (class "Default")
      (node (ref "Q1") (pin "2") (pinfunction "B_2") (pintype "passive"))
      (node (ref "R1") (pin "2") (pinfunction "2_2") (pintype "passive"))
    )
    (net (code "97") (name "Net-(Q1-C)") (class "Default")
      (node (ref "Jumper1") (pin "1") (pinfunction "1_1") (pintype "passive"))
      (node (ref "Q1") (pin "1") (pinfunction "C_1") (pintype "passive"))
    )
    (net (code "98") (name "Net-(Reset1-NO)") (class "Default")
      (node (ref "P1") (pin "5") (pinfunction "5_5") (pintype "passive"))
      (node (ref "R16") (pin "2") (pinfunction "2_2") (pintype "passive"))
      (node (ref "Reset1") (pin "2") (pinfunction "NO_2") (pintype "passive"))
      (node (ref "U3") (pin "90") (pinfunction "~{RESET}_90") (pintype "input"))
    )
    (net (code "99") (name "Net-(U3-PDI)") (class "Default")
      (node (ref "P1") (pin "1") (pinfunction "1_1") (pintype "passive"))
      (node (ref "U3") (pin "89") (pinfunction "PDI_89") (pintype "passive"))
    )
    (net (code "100") (name "unconnected-(P1-Pad3)") (class "Default")
      (node (ref "P1") (pin "3") (pinfunction "3_3") (pintype "passive"))
    )
    (net (code "101") (name "unconnected-(P1-Pad4)") (class "Default")
      (node (ref "P1") (pin "4") (pinfunction "4_4") (pintype "passive"))
    )
    (net (code "102") (name "unconnected-(U3-XTAL1-Pad92)") (class "Default")
      (node (ref "U3") (pin "92") (pinfunction "XTAL1_92") (pintype "passive"))
    )
    (net (code "103") (name "unconnected-(U3-XTAL2-Pad91)") (class "Default")
      (node (ref "U3") (pin "91") (pinfunction "XTAL2_91") (pintype "passive"))
    )
  )
)
